# SCH_Mathuoosh-PCB_2024-10-10.net
KiCad netlist of a schematic drawn in EasyEDA
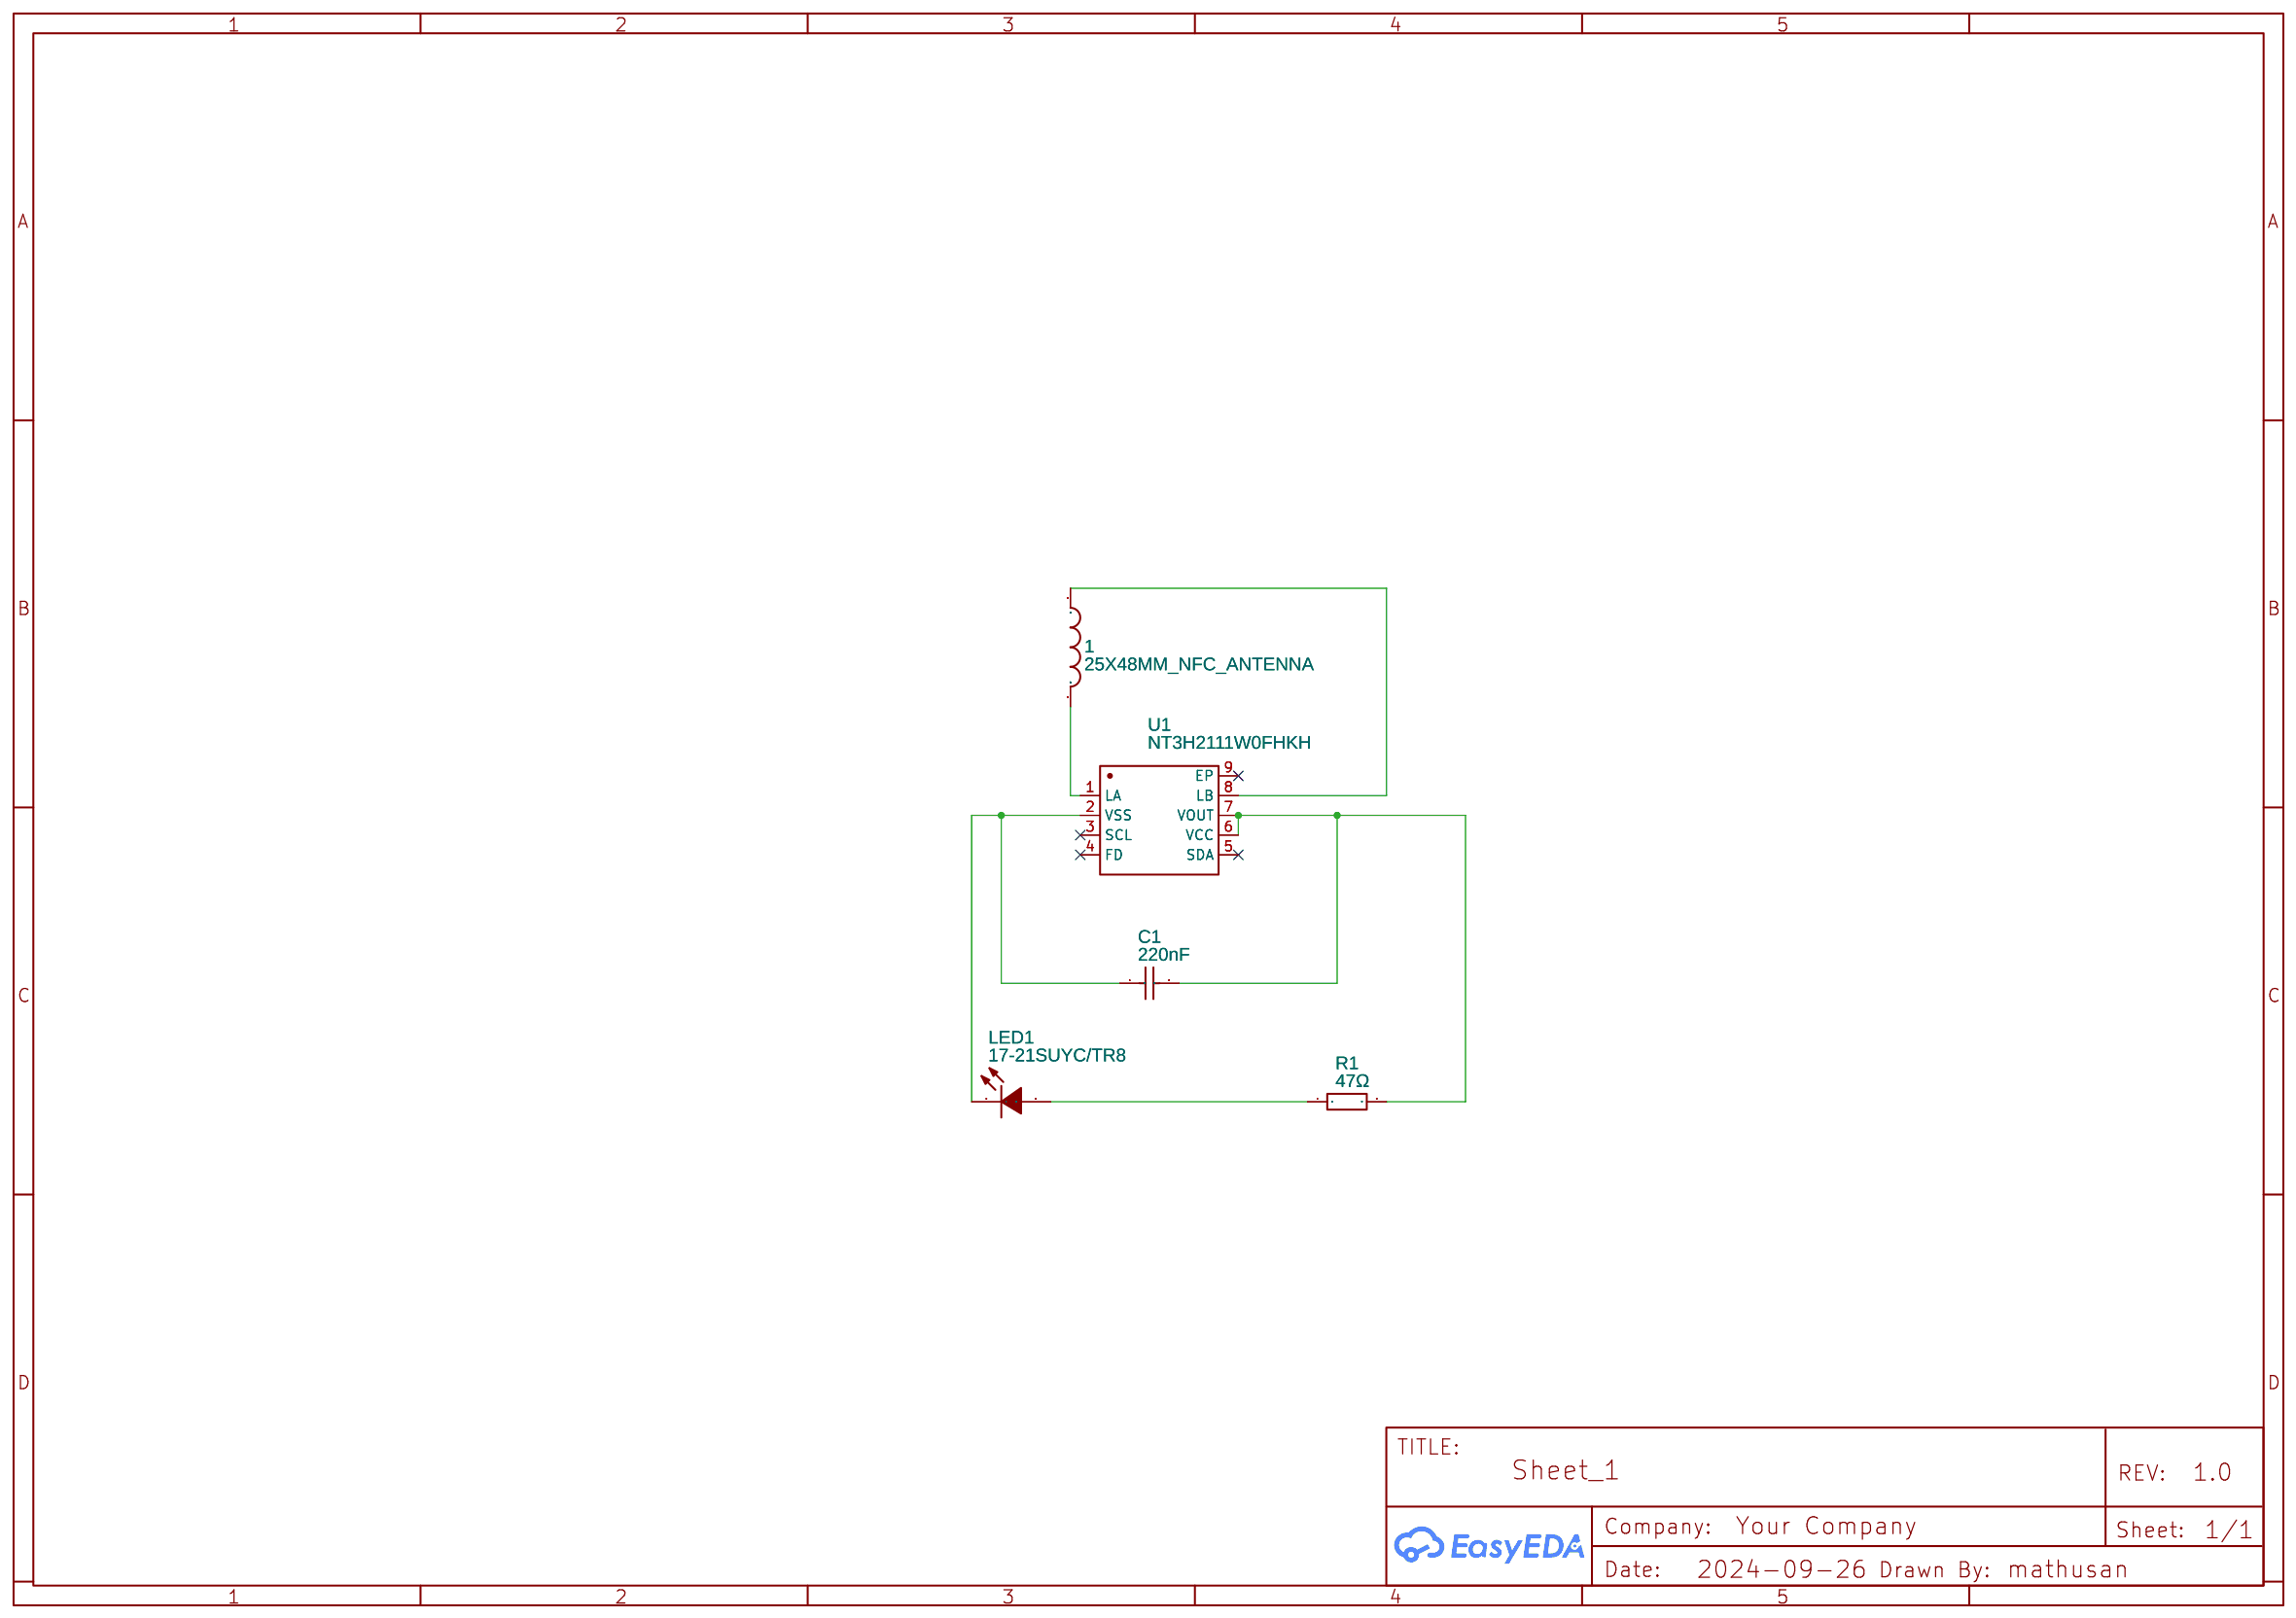
[diagram p0: schematic sheet]

(export (version "E")
  (design (tool "Eeschema 10.0.6"))
  (components
    (comp (ref "1") (value "25X48MM_NFC_ANTENNA") (libsource (lib "") (part "25X48MM_NFC_ANTENNA")))
    (comp (ref "C1")
      (value "220nF")
      (fields
        (field (name "Manufacturer Part") "CL10B224KA8NNNC")
        (field (name "Manufacturer") "SAMSUNG(三星)")
      )
      (libsource (lib "") (part "CL10B224KA8NNNC"))
    )
    (comp (ref "LED1")
      (value "17-21SUYC/TR8")
      (fields (field (name "Manufacturer Part") "KT-0805黄灯") (field (name "Manufacturer") "KENTO"))
      (libsource (lib "") (part "17-21SUYC/TR8"))
    )
    (comp (ref "R1")
      (value "47Ω")
      (fields
        (field (name "Manufacturer Part") "0603WAF470JT5E")
        (field (name "Manufacturer") "UNI-ROYAL(厚声)")
      )
      (libsource (lib "") (part "0603WAF470JT5E"))
    )
    (comp (ref "U1")
      (value "NT3H2111W0FHKH")
      (fields (field (name "Manufacturer") "NXP(恩智浦)"))
      (libsource (lib "") (part "NT3H2111W0FHKH"))
    )
  )
  (nets
    (net (code "1") (name "Net-(LED1-+)") (class "Default")
      (node (ref "LED1") (pin "1") (pinfunction "+_1") (pintype "unspecified"))
      (node (ref "R1") (pin "1") (pinfunction "1_1") (pintype "input"))
    )
    (net (code "2") (name "Net-(LED1--)") (class "Default")
      (node (ref "C1") (pin "1") (pinfunction "1_1") (pintype "input"))
      (node (ref "LED1") (pin "2") (pinfunction "-_2") (pintype "unspecified"))
      (node (ref "U1") (pin "2") (pinfunction "VSS_2") (pintype "unspecified"))
    )
    (net (code "3") (name "Net-(U1-LA)") (class "Default")
      (node (ref "1") (pin "P$2") (pinfunction "P$2_P$2") (pintype "bidirectional"))
      (node (ref "U1") (pin "1") (pinfunction "LA_1") (pintype "unspecified"))
    )
    (net (code "4") (name "Net-(U1-LB)") (class "Default")
      (node (ref "1") (pin "P$1") (pinfunction "P$1_P$1") (pintype "bidirectional"))
      (node (ref "U1") (pin "8") (pinfunction "LB_8") (pintype "unspecified"))
    )
    (net (code "5") (name "Net-(U1-VCC)") (class "Default")
      (node (ref "C1") (pin "2") (pinfunction "2_2") (pintype "input"))
      (node (ref "R1") (pin "2") (pinfunction "2_2") (pintype "input"))
      (node (ref "U1") (pin "6") (pinfunction "VCC_6") (pintype "unspecified"))
      (node (ref "U1") (pin "7") (pinfunction "VOUT_7") (pintype "unspecified"))
    )
    (net (code "6") (name "unconnected-(U1-EP-Pad9)") (class "Default")
      (node (ref "U1") (pin "9") (pinfunction "EP_9") (pintype "unspecified+no_connect"))
    )
    (net (code "7") (name "unconnected-(U1-FD-Pad4)") (class "Default")
      (node (ref "U1") (pin "4") (pinfunction "FD_4") (pintype "unspecified+no_connect"))
    )
    (net (code "8") (name "unconnected-(U1-SCL-Pad3)") (class "Default")
      (node (ref "U1") (pin "3") (pinfunction "SCL_3") (pintype "unspecified+no_connect"))
    )
    (net (code "9") (name "unconnected-(U1-SDA-Pad5)") (class "Default")
      (node (ref "U1") (pin "5") (pinfunction "SDA_5") (pintype "unspecified+no_connect"))
    )
  )
)
